# cannonrobot.net
KiCad netlist of a schematic drawn in Altium Designer
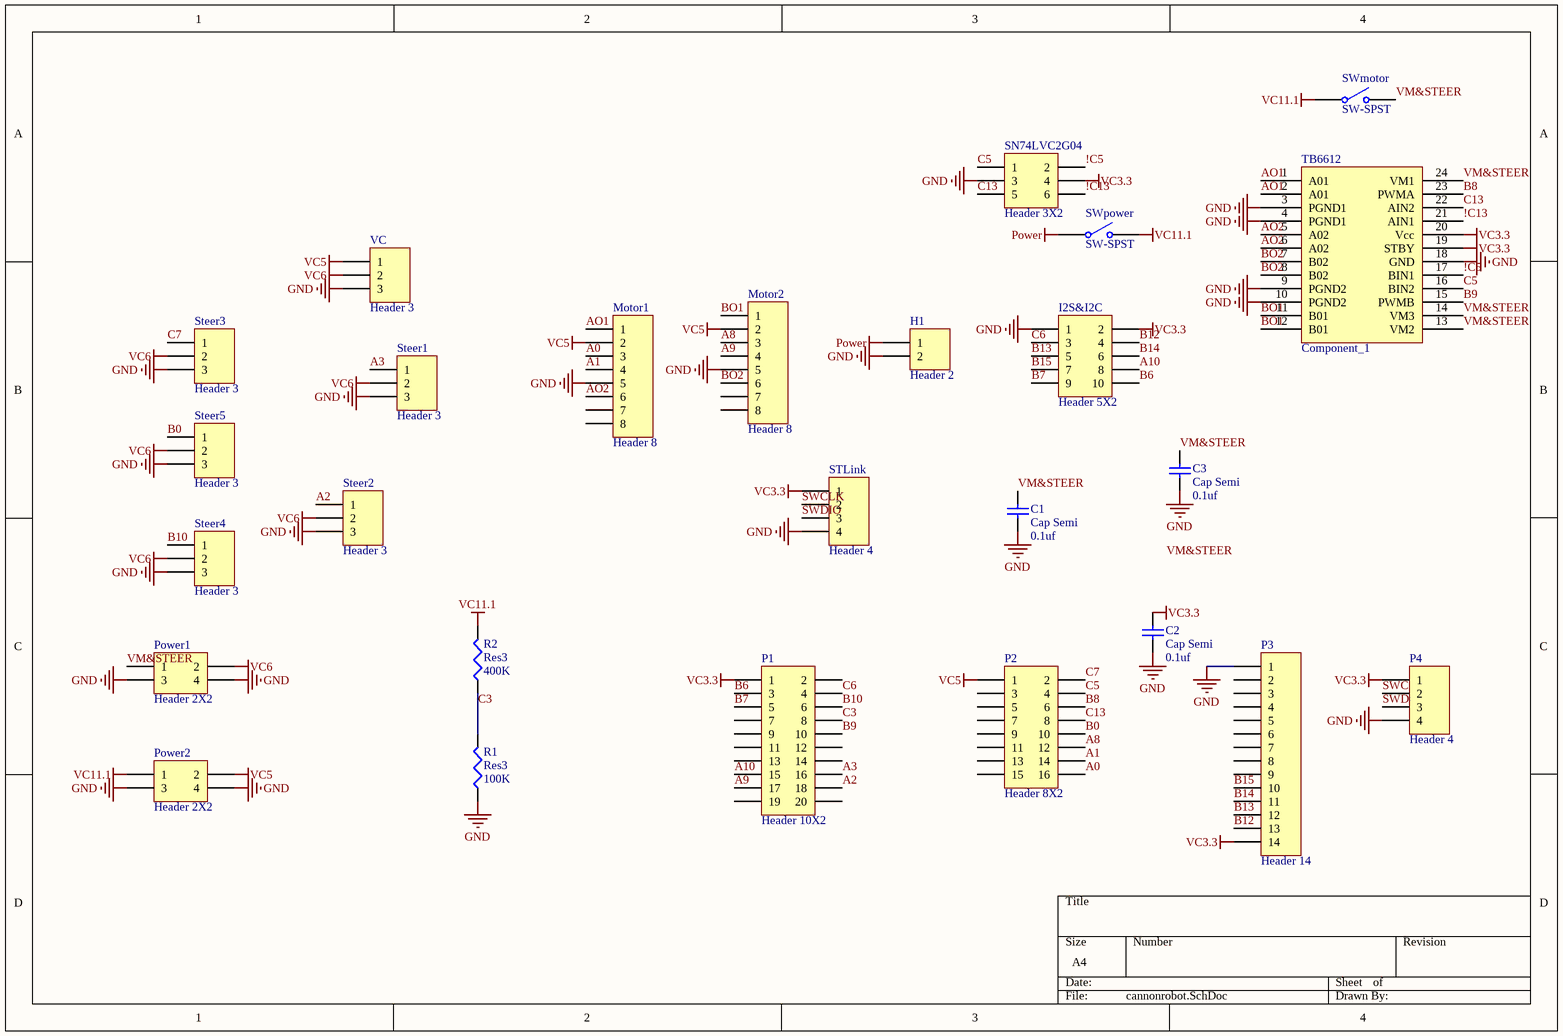
[diagram p0: cannonrobot.SchDoc]

(export (version "E")
  (design (tool "Eeschema 10.0.6"))
  (components
    (comp (ref "C1")
      (value "Cap Semi")
      (footprint "CAPC3225L")
      (description "Capacitor (Semiconductor SIM Model)")
      (fields (field (name "ALTIUM_VALUE") "0.1uf") (field (name "PUBLISHER") "Altium Limited"))
      (libsource (lib "Miscellaneous Devices") (part "Cap Semi"))
    )
    (comp (ref "C2")
      (value "Cap Semi")
      (footprint "CAPC2512L")
      (description "Capacitor (Semiconductor SIM Model)")
      (fields (field (name "ALTIUM_VALUE") "0.1uf") (field (name "PUBLISHER") "Altium Limited"))
      (libsource (lib "Miscellaneous Devices") (part "Cap Semi"))
    )
    (comp (ref "C3")
      (value "Cap Semi")
      (footprint "CAPC2512L")
      (description "Capacitor (Semiconductor SIM Model)")
      (fields (field (name "ALTIUM_VALUE") "0.1uf") (field (name "PUBLISHER") "Altium Limited"))
      (libsource (lib "Miscellaneous Devices") (part "Cap Semi"))
    )
    (comp (ref "H1")
      (value "Header 2")
      (footprint "电源接口:PCBComponent_1")
      (description "Header, 2-Pin")
      (fields (field (name "PUBLISHER") "Altium Limited"))
      (libsource (lib "Miscellaneous Connectors") (part "Header 2"))
    )
    (comp (ref "I2S&I2C")
      (value "Header 5X2")
      (footprint "HDR2X5")
      (description "Header, 5-Pin, Dual row")
      (fields (field (name "PUBLISHER") "Altium Limited"))
      (libsource (lib "Miscellaneous Connectors") (part "Header 5X2"))
    )
    (comp (ref "Motor1")
      (value "Header 8")
      (footprint "J_JAT_A1250WV-S-06P:J_JAT_A1250WV-S-06P")
      (description "Header, 8-Pin")
      (fields (field (name "PUBLISHER") "Altium Limited"))
      (libsource (lib "Miscellaneous Connectors") (part "Header 8"))
    )
    (comp (ref "Motor2")
      (value "Header 8")
      (footprint "J_JAT_A1250WV-S-06P:J_JAT_A1250WV-S-06P")
      (description "Header, 8-Pin")
      (fields (field (name "PUBLISHER") "Altium Limited"))
      (libsource (lib "Miscellaneous Connectors") (part "Header 8"))
    )
    (comp (ref "P1")
      (value "Header 10X2")
      (footprint "HDR2X10")
      (description "Header, 10-Pin, Dual row")
      (fields (field (name "PUBLISHER") "Altium Limited"))
      (libsource (lib "Miscellaneous Connectors") (part "Header 10X2"))
    )
    (comp (ref "P2")
      (value "Header 8X2")
      (footprint "HDR2X8")
      (description "Header, 8-Pin, Dual row")
      (fields (field (name "PUBLISHER") "Altium Limited"))
      (libsource (lib "Miscellaneous Connectors") (part "Header 8X2"))
    )
    (comp (ref "P3")
      (value "Header 14")
      (footprint "HDR1X14")
      (description "Header, 14-Pin")
      (fields (field (name "PUBLISHER") "Altium Limited"))
      (libsource (lib "Miscellaneous Connectors") (part "Header 14"))
    )
    (comp (ref "P4")
      (value "Header 4")
      (footprint "HDR1X4")
      (description "Header, 4-Pin")
      (fields (field (name "PUBLISHER") "Altium Limited"))
      (libsource (lib "Miscellaneous Connectors") (part "Header 4"))
    )
    (comp (ref "Power1")
      (value "Header 2X2")
      (footprint "电源3.3V:PCBComponent_1")
      (description "Header, 2-Pin, Dual row")
      (fields (field (name "PUBLISHER") "Altium Limited"))
      (libsource (lib "Miscellaneous Connectors") (part "Header 2X2"))
    )
    (comp (ref "Power2")
      (value "Header 2X2")
      (footprint "电源3.3V:PCBComponent_1")
      (description "Header, 2-Pin, Dual row")
      (fields (field (name "PUBLISHER") "Altium Limited"))
      (libsource (lib "Miscellaneous Connectors") (part "Header 2X2"))
    )
    (comp (ref "R1")
      (value "Res3")
      (footprint "RESC1608L")
      (description "Resistor")
      (fields (field (name "ALTIUM_VALUE") "100K") (field (name "PUBLISHER") "Altium Limited"))
      (libsource (lib "Miscellaneous Devices") (part "Res3"))
    )
    (comp (ref "R2")
      (value "Res3")
      (footprint "RESC1608L")
      (description "Resistor")
      (fields (field (name "ALTIUM_VALUE") "400K") (field (name "PUBLISHER") "Altium Limited"))
      (libsource (lib "Miscellaneous Devices") (part "Res3"))
    )
    (comp (ref "SN74LVC2G04")
      (value "Header 3X2")
      (footprint "SOT23-6:PCBComponent_1")
      (description "Header, 3-Pin, Dual row")
      (fields (field (name "PUBLISHER") "Altium Limited"))
      (libsource (lib "Miscellaneous Connectors") (part "Header 3X2"))
    )
    (comp (ref "Steer1")
      (value "Header 3")
      (footprint "HDR1X3")
      (description "Header, 3-Pin")
      (fields (field (name "PUBLISHER") "Altium Limited"))
      (libsource (lib "Miscellaneous Connectors") (part "Header 3"))
    )
    (comp (ref "Steer2")
      (value "Header 3")
      (footprint "HDR1X3")
      (description "Header, 3-Pin")
      (fields (field (name "PUBLISHER") "Altium Limited"))
      (libsource (lib "Miscellaneous Connectors") (part "Header 3"))
    )
    (comp (ref "Steer3")
      (value "Header 3")
      (footprint "HDR1X3")
      (description "Header, 3-Pin")
      (fields (field (name "PUBLISHER") "Altium Limited"))
      (libsource (lib "Miscellaneous Connectors") (part "Header 3"))
    )
    (comp (ref "Steer4")
      (value "Header 3")
      (footprint "HDR1X3")
      (description "Header, 3-Pin")
      (fields (field (name "PUBLISHER") "Altium Limited"))
      (libsource (lib "Miscellaneous Connectors") (part "Header 3"))
    )
    (comp (ref "Steer5")
      (value "Header 3")
      (footprint "HDR1X3")
      (description "Header, 3-Pin")
      (fields (field (name "PUBLISHER") "Altium Limited"))
      (libsource (lib "Miscellaneous Connectors") (part "Header 3"))
    )
    (comp (ref "STLink")
      (value "Header 4")
      (footprint "HDR1X4")
      (description "Header, 4-Pin")
      (fields (field (name "PUBLISHER") "Altium Limited"))
      (libsource (lib "Miscellaneous Connectors") (part "Header 4"))
    )
    (comp (ref "SWmotor")
      (value "SW-SPST")
      (footprint "拨动开关:PCBComponent_1")
      (description "Single-Pole, Single-Throw Switch")
      (fields (field (name "PUBLISHER") "Altium Limited"))
      (libsource (lib "Miscellaneous Devices") (part "SW-SPST"))
    )
    (comp (ref "SWpower")
      (value "SW-SPST")
      (footprint "拨动开关:PCBComponent_1")
      (description "Single-Pole, Single-Throw Switch")
      (fields (field (name "PUBLISHER") "Altium Limited"))
      (libsource (lib "Miscellaneous Devices") (part "SW-SPST"))
    )
    (comp (ref "TB6612")
      (value "Component_1")
      (footprint "SSOP24:SSOP24 - duplicate")
      (libsource (lib "TB6612") (part "Component_1"))
    )
    (comp (ref "VC")
      (value "Header 3")
      (footprint "HDR1X3")
      (description "Header, 3-Pin")
      (fields (field (name "PUBLISHER") "Altium Limited"))
      (libsource (lib "Miscellaneous Connectors") (part "Header 3"))
    )
  )
  (nets
    (net (code "1") (name "/!C5") (class "Default")
      (node (ref "SN74LVC2G04") (pin "2") (pinfunction "2_2") (pintype "passive"))
      (node (ref "TB6612") (pin "17") (pinfunction "BIN1_17") (pintype "passive"))
    )
    (net (code "2") (name "/!C13") (class "Default")
      (node (ref "SN74LVC2G04") (pin "6") (pinfunction "6_6") (pintype "passive"))
      (node (ref "TB6612") (pin "21") (pinfunction "AIN1_21") (pintype "passive"))
    )
    (net (code "3") (name "/A0") (class "Default")
      (node (ref "Motor1") (pin "3") (pinfunction "3_3") (pintype "passive"))
      (node (ref "P2") (pin "16") (pinfunction "16_16") (pintype "passive"))
    )
    (net (code "4") (name "/A1") (class "Default")
      (node (ref "Motor1") (pin "4") (pinfunction "4_4") (pintype "passive"))
      (node (ref "P2") (pin "14") (pinfunction "14_14") (pintype "passive"))
    )
    (net (code "5") (name "/A2") (class "Default")
      (node (ref "P1") (pin "18") (pinfunction "18_18") (pintype "passive"))
      (node (ref "Steer2") (pin "1") (pinfunction "1_1") (pintype "passive"))
    )
    (net (code "6") (name "/A3") (class "Default")
      (node (ref "P1") (pin "16") (pinfunction "16_16") (pintype "passive"))
      (node (ref "Steer1") (pin "1") (pinfunction "1_1") (pintype "passive"))
    )
    (net (code "7") (name "/A8") (class "Default")
      (node (ref "Motor2") (pin "3") (pinfunction "3_3") (pintype "passive"))
      (node (ref "P2") (pin "12") (pinfunction "12_12") (pintype "passive"))
    )
    (net (code "8") (name "/A9") (class "Default")
      (node (ref "Motor2") (pin "4") (pinfunction "4_4") (pintype "passive"))
      (node (ref "P1") (pin "17") (pinfunction "17_17") (pintype "passive"))
    )
    (net (code "9") (name "/A10") (class "Default")
      (node (ref "I2S&I2C") (pin "8") (pinfunction "8_8") (pintype "passive"))
      (node (ref "P1") (pin "15") (pinfunction "15_15") (pintype "passive"))
    )
    (net (code "10") (name "/AO1") (class "Default")
      (node (ref "Motor1") (pin "1") (pinfunction "1_1") (pintype "passive"))
      (node (ref "TB6612") (pin "1") (pinfunction "A01_1") (pintype "passive"))
      (node (ref "TB6612") (pin "2") (pinfunction "A01_2") (pintype "passive"))
    )
    (net (code "11") (name "/AO2") (class "Default")
      (node (ref "Motor1") (pin "6") (pinfunction "6_6") (pintype "passive"))
      (node (ref "TB6612") (pin "5") (pinfunction "A02_5") (pintype "passive"))
      (node (ref "TB6612") (pin "6") (pinfunction "A02_6") (pintype "passive"))
    )
    (net (code "12") (name "/B0") (class "Default")
      (node (ref "P2") (pin "10") (pinfunction "10_10") (pintype "passive"))
      (node (ref "Steer5") (pin "1") (pinfunction "1_1") (pintype "passive"))
    )
    (net (code "13") (name "/B6") (class "Default")
      (node (ref "I2S&I2C") (pin "10") (pinfunction "10_10") (pintype "passive"))
      (node (ref "P1") (pin "3") (pinfunction "3_3") (pintype "passive"))
    )
    (net (code "14") (name "/B7") (class "Default")
      (node (ref "I2S&I2C") (pin "9") (pinfunction "9_9") (pintype "passive"))
      (node (ref "P1") (pin "5") (pinfunction "5_5") (pintype "passive"))
    )
    (net (code "15") (name "/B8") (class "Default")
      (node (ref "P2") (pin "6") (pinfunction "6_6") (pintype "passive"))
      (node (ref "TB6612") (pin "23") (pinfunction "PWMA_23") (pintype "passive"))
    )
    (net (code "16") (name "/B9") (class "Default")
      (node (ref "P1") (pin "10") (pinfunction "10_10") (pintype "passive"))
      (node (ref "TB6612") (pin "15") (pinfunction "PWMB_15") (pintype "passive"))
    )
    (net (code "17") (name "/B10") (class "Default")
      (node (ref "P1") (pin "6") (pinfunction "6_6") (pintype "passive"))
      (node (ref "Steer4") (pin "1") (pinfunction "1_1") (pintype "passive"))
    )
    (net (code "18") (name "/B12") (class "Default")
      (node (ref "I2S&I2C") (pin "4") (pinfunction "4_4") (pintype "passive"))
      (node (ref "P3") (pin "13") (pinfunction "13_13") (pintype "passive"))
    )
    (net (code "19") (name "/B13") (class "Default")
      (node (ref "I2S&I2C") (pin "5") (pinfunction "5_5") (pintype "passive"))
      (node (ref "P3") (pin "12") (pinfunction "12_12") (pintype "passive"))
    )
    (net (code "20") (name "/B14") (class "Default")
      (node (ref "I2S&I2C") (pin "6") (pinfunction "6_6") (pintype "passive"))
      (node (ref "P3") (pin "11") (pinfunction "11_11") (pintype "passive"))
    )
    (net (code "21") (name "/B15") (class "Default")
      (node (ref "I2S&I2C") (pin "7") (pinfunction "7_7") (pintype "passive"))
      (node (ref "P3") (pin "10") (pinfunction "10_10") (pintype "passive"))
    )
    (net (code "22") (name "/BO1") (class "Default")
      (node (ref "Motor2") (pin "1") (pinfunction "1_1") (pintype "passive"))
      (node (ref "TB6612") (pin "11") (pinfunction "B01_11") (pintype "passive"))
      (node (ref "TB6612") (pin "12") (pinfunction "B01_12") (pintype "passive"))
    )
    (net (code "23") (name "/BO2") (class "Default")
      (node (ref "Motor2") (pin "6") (pinfunction "6_6") (pintype "passive"))
      (node (ref "TB6612") (pin "7") (pinfunction "B02_7") (pintype "passive"))
      (node (ref "TB6612") (pin "8") (pinfunction "B02_8") (pintype "passive"))
    )
    (net (code "24") (name "/C3") (class "Default")
      (node (ref "P1") (pin "8") (pinfunction "8_8") (pintype "passive"))
      (node (ref "R1") (pin "2") (pinfunction "2_2") (pintype "passive"))
      (node (ref "R2") (pin "1") (pinfunction "1_1") (pintype "passive"))
    )
    (net (code "25") (name "/C5") (class "Default")
      (node (ref "P2") (pin "4") (pinfunction "4_4") (pintype "passive"))
      (node (ref "SN74LVC2G04") (pin "1") (pinfunction "1_1") (pintype "passive"))
      (node (ref "TB6612") (pin "16") (pinfunction "BIN2_16") (pintype "passive"))
    )
    (net (code "26") (name "/C6") (class "Default")
      (node (ref "I2S&I2C") (pin "3") (pinfunction "3_3") (pintype "passive"))
      (node (ref "P1") (pin "4") (pinfunction "4_4") (pintype "passive"))
    )
    (net (code "27") (name "/C7") (class "Default")
      (node (ref "P2") (pin "2") (pinfunction "2_2") (pintype "passive"))
      (node (ref "Steer3") (pin "1") (pinfunction "1_1") (pintype "passive"))
    )
    (net (code "28") (name "/C13") (class "Default")
      (node (ref "P2") (pin "8") (pinfunction "8_8") (pintype "passive"))
      (node (ref "SN74LVC2G04") (pin "5") (pinfunction "5_5") (pintype "passive"))
      (node (ref "TB6612") (pin "22") (pinfunction "AIN2_22") (pintype "passive"))
    )
    (net (code "29") (name "/SWCLK") (class "Default")
      (node (ref "P4") (pin "2") (pinfunction "2_2") (pintype "passive"))
      (node (ref "STLink") (pin "2") (pinfunction "2_2") (pintype "passive"))
    )
    (net (code "30") (name "/SWDIO") (class "Default")
      (node (ref "P4") (pin "3") (pinfunction "3_3") (pintype "passive"))
      (node (ref "STLink") (pin "3") (pinfunction "3_3") (pintype "passive"))
    )
    (net (code "31") (name "/VM&STEER") (class "Default")
      (node (ref "C1") (pin "2") (pinfunction "2_2") (pintype "passive"))
      (node (ref "C3") (pin "2") (pinfunction "2_2") (pintype "passive"))
      (node (ref "Power1") (pin "1") (pinfunction "1_1") (pintype "passive"))
      (node (ref "SWmotor") (pin "2") (pinfunction "NO_2") (pintype "passive"))
      (node (ref "TB6612") (pin "13") (pinfunction "VM2_13") (pintype "passive"))
      (node (ref "TB6612") (pin "14") (pinfunction "VM3_14") (pintype "passive"))
      (node (ref "TB6612") (pin "24") (pinfunction "VM1_24") (pintype "passive"))
    )
    (net (code "32") (name "GND") (class "Default")
      (node (ref "C1") (pin "1") (pinfunction "1_1") (pintype "passive"))
      (node (ref "C2") (pin "1") (pinfunction "1_1") (pintype "passive"))
      (node (ref "C3") (pin "1") (pinfunction "1_1") (pintype "passive"))
      (node (ref "H1") (pin "2") (pinfunction "2_2") (pintype "passive"))
      (node (ref "I2S&I2C") (pin "1") (pinfunction "1_1") (pintype "passive"))
      (node (ref "Motor1") (pin "5") (pinfunction "5_5") (pintype "passive"))
      (node (ref "Motor2") (pin "5") (pinfunction "5_5") (pintype "passive"))
      (node (ref "P3") (pin "1") (pinfunction "1_1") (pintype "passive"))
      (node (ref "P4") (pin "4") (pinfunction "4_4") (pintype "passive"))
      (node (ref "Power1") (pin "3") (pinfunction "3_3") (pintype "passive"))
      (node (ref "Power1") (pin "4") (pinfunction "4_4") (pintype "passive"))
      (node (ref "Power2") (pin "3") (pinfunction "3_3") (pintype "passive"))
      (node (ref "Power2") (pin "4") (pinfunction "4_4") (pintype "passive"))
      (node (ref "R1") (pin "1") (pinfunction "1_1") (pintype "passive"))
      (node (ref "SN74LVC2G04") (pin "3") (pinfunction "3_3") (pintype "passive"))
      (node (ref "STLink") (pin "4") (pinfunction "4_4") (pintype "passive"))
      (node (ref "Steer1") (pin "3") (pinfunction "3_3") (pintype "passive"))
      (node (ref "Steer2") (pin "3") (pinfunction "3_3") (pintype "passive"))
      (node (ref "Steer3") (pin "3") (pinfunction "3_3") (pintype "passive"))
      (node (ref "Steer4") (pin "3") (pinfunction "3_3") (pintype "passive"))
      (node (ref "Steer5") (pin "3") (pinfunction "3_3") (pintype "passive"))
      (node (ref "TB6612") (pin "10") (pinfunction "PGND2_10") (pintype "passive"))
      (node (ref "TB6612") (pin "18") (pinfunction "GND_18") (pintype "passive"))
      (node (ref "TB6612") (pin "3") (pinfunction "PGND1_3") (pintype "passive"))
      (node (ref "TB6612") (pin "4") (pinfunction "PGND1_4") (pintype "passive"))
      (node (ref "TB6612") (pin "9") (pinfunction "PGND2_9") (pintype "passive"))
      (node (ref "VC") (pin "3") (pinfunction "3_3") (pintype "passive"))
    )
    (net (code "33") (name "Power") (class "Default")
      (node (ref "H1") (pin "1") (pinfunction "1_1") (pintype "passive"))
      (node (ref "SWpower") (pin "1") (pinfunction "COMMON_1") (pintype "passive"))
    )
    (net (code "34") (name "VC3.3") (class "Default")
      (node (ref "C2") (pin "2") (pinfunction "2_2") (pintype "passive"))
      (node (ref "I2S&I2C") (pin "2") (pinfunction "2_2") (pintype "passive"))
      (node (ref "P1") (pin "1") (pinfunction "1_1") (pintype "passive"))
      (node (ref "P3") (pin "14") (pinfunction "14_14") (pintype "passive"))
      (node (ref "P4") (pin "1") (pinfunction "1_1") (pintype "passive"))
      (node (ref "SN74LVC2G04") (pin "4") (pinfunction "4_4") (pintype "passive"))
      (node (ref "STLink") (pin "1") (pinfunction "1_1") (pintype "passive"))
      (node (ref "TB6612") (pin "19") (pinfunction "STBY_19") (pintype "passive"))
      (node (ref "TB6612") (pin "20") (pinfunction "Vcc_20") (pintype "passive"))
    )
    (net (code "35") (name "VC5") (class "Default")
      (node (ref "Motor1") (pin "2") (pinfunction "2_2") (pintype "passive"))
      (node (ref "Motor2") (pin "2") (pinfunction "2_2") (pintype "passive"))
      (node (ref "P2") (pin "1") (pinfunction "1_1") (pintype "passive"))
      (node (ref "Power2") (pin "2") (pinfunction "2_2") (pintype "passive"))
      (node (ref "VC") (pin "1") (pinfunction "1_1") (pintype "passive"))
    )
    (net (code "36") (name "VC6") (class "Default")
      (node (ref "Power1") (pin "2") (pinfunction "2_2") (pintype "passive"))
      (node (ref "Steer1") (pin "2") (pinfunction "2_2") (pintype "passive"))
      (node (ref "Steer2") (pin "2") (pinfunction "2_2") (pintype "passive"))
      (node (ref "Steer3") (pin "2") (pinfunction "2_2") (pintype "passive"))
      (node (ref "Steer4") (pin "2") (pinfunction "2_2") (pintype "passive"))
      (node (ref "Steer5") (pin "2") (pinfunction "2_2") (pintype "passive"))
      (node (ref "VC") (pin "2") (pinfunction "2_2") (pintype "passive"))
    )
    (net (code "37") (name "VC11.1") (class "Default")
      (node (ref "Power2") (pin "1") (pinfunction "1_1") (pintype "passive"))
      (node (ref "R2") (pin "2") (pinfunction "2_2") (pintype "passive"))
      (node (ref "SWmotor") (pin "1") (pinfunction "COMMON_1") (pintype "passive"))
      (node (ref "SWpower") (pin "2") (pinfunction "NO_2") (pintype "passive"))
    )
    (net (code "38") (name "unconnected-(Motor1-Pad7)") (class "Default")
      (node (ref "Motor1") (pin "7") (pinfunction "7_7") (pintype "passive"))
    )
    (net (code "39") (name "unconnected-(Motor1-Pad8)") (class "Default")
      (node (ref "Motor1") (pin "8") (pinfunction "8_8") (pintype "passive"))
    )
    (net (code "40") (name "unconnected-(Motor2-Pad7)") (class "Default")
      (node (ref "Motor2") (pin "7") (pinfunction "7_7") (pintype "passive"))
    )
    (net (code "41") (name "unconnected-(Motor2-Pad8)") (class "Default")
      (node (ref "Motor2") (pin "8") (pinfunction "8_8") (pintype "passive"))
    )
    (net (code "42") (name "unconnected-(P1-Pad2)") (class "Default")
      (node (ref "P1") (pin "2") (pinfunction "2_2") (pintype "passive"))
    )
    (net (code "43") (name "unconnected-(P1-Pad7)") (class "Default")
      (node (ref "P1") (pin "7") (pinfunction "7_7") (pintype "passive"))
    )
    (net (code "44") (name "unconnected-(P1-Pad9)") (class "Default")
      (node (ref "P1") (pin "9") (pinfunction "9_9") (pintype "passive"))
    )
    (net (code "45") (name "unconnected-(P1-Pad11)") (class "Default")
      (node (ref "P1") (pin "11") (pinfunction "11_11") (pintype "passive"))
    )
    (net (code "46") (name "unconnected-(P1-Pad12)") (class "Default")
      (node (ref "P1") (pin "12") (pinfunction "12_12") (pintype "passive"))
    )
    (net (code "47") (name "unconnected-(P1-Pad13)") (class "Default")
      (node (ref "P1") (pin "13") (pinfunction "13_13") (pintype "passive"))
    )
    (net (code "48") (name "unconnected-(P1-Pad14)") (class "Default")
      (node (ref "P1") (pin "14") (pinfunction "14_14") (pintype "passive"))
    )
    (net (code "49") (name "unconnected-(P1-Pad19)") (class "Default")
      (node (ref "P1") (pin "19") (pinfunction "19_19") (pintype "passive"))
    )
    (net (code "50") (name "unconnected-(P1-Pad20)") (class "Default")
      (node (ref "P1") (pin "20") (pinfunction "20_20") (pintype "passive"))
    )
    (net (code "51") (name "unconnected-(P2-Pad3)") (class "Default")
      (node (ref "P2") (pin "3") (pinfunction "3_3") (pintype "passive"))
    )
    (net (code "52") (name "unconnected-(P2-Pad5)") (class "Default")
      (node (ref "P2") (pin "5") (pinfunction "5_5") (pintype "passive"))
    )
    (net (code "53") (name "unconnected-(P2-Pad7)") (class "Default")
      (node (ref "P2") (pin "7") (pinfunction "7_7") (pintype "passive"))
    )
    (net (code "54") (name "unconnected-(P2-Pad9)") (class "Default")
      (node (ref "P2") (pin "9") (pinfunction "9_9") (pintype "passive"))
    )
    (net (code "55") (name "unconnected-(P2-Pad11)") (class "Default")
      (node (ref "P2") (pin "11") (pinfunction "11_11") (pintype "passive"))
    )
    (net (code "56") (name "unconnected-(P2-Pad13)") (class "Default")
      (node (ref "P2") (pin "13") (pinfunction "13_13") (pintype "passive"))
    )
    (net (code "57") (name "unconnected-(P2-Pad15)") (class "Default")
      (node (ref "P2") (pin "15") (pinfunction "15_15") (pintype "passive"))
    )
    (net (code "58") (name "unconnected-(P3-Pad2)") (class "Default")
      (node (ref "P3") (pin "2") (pinfunction "2_2") (pintype "passive"))
    )
    (net (code "59") (name "unconnected-(P3-Pad3)") (class "Default")
      (node (ref "P3") (pin "3") (pinfunction "3_3") (pintype "passive"))
    )
    (net (code "60") (name "unconnected-(P3-Pad4)") (class "Default")
      (node (ref "P3") (pin "4") (pinfunction "4_4") (pintype "passive"))
    )
    (net (code "61") (name "unconnected-(P3-Pad5)") (class "Default")
      (node (ref "P3") (pin "5") (pinfunction "5_5") (pintype "passive"))
    )
    (net (code "62") (name "unconnected-(P3-Pad6)") (class "Default")
      (node (ref "P3") (pin "6") (pinfunction "6_6") (pintype "passive"))
    )
    (net (code "63") (name "unconnected-(P3-Pad7)") (class "Default")
      (node (ref "P3") (pin "7") (pinfunction "7_7") (pintype "passive"))
    )
    (net (code "64") (name "unconnected-(P3-Pad8)") (class "Default")
      (node (ref "P3") (pin "8") (pinfunction "8_8") (pintype "passive"))
    )
    (net (code "65") (name "unconnected-(P3-Pad9)") (class "Default")
      (node (ref "P3") (pin "9") (pinfunction "9_9") (pintype "passive"))
    )
  )
)
